# USB_Hub.net
KiCad netlist of a schematic drawn in Altium Designer
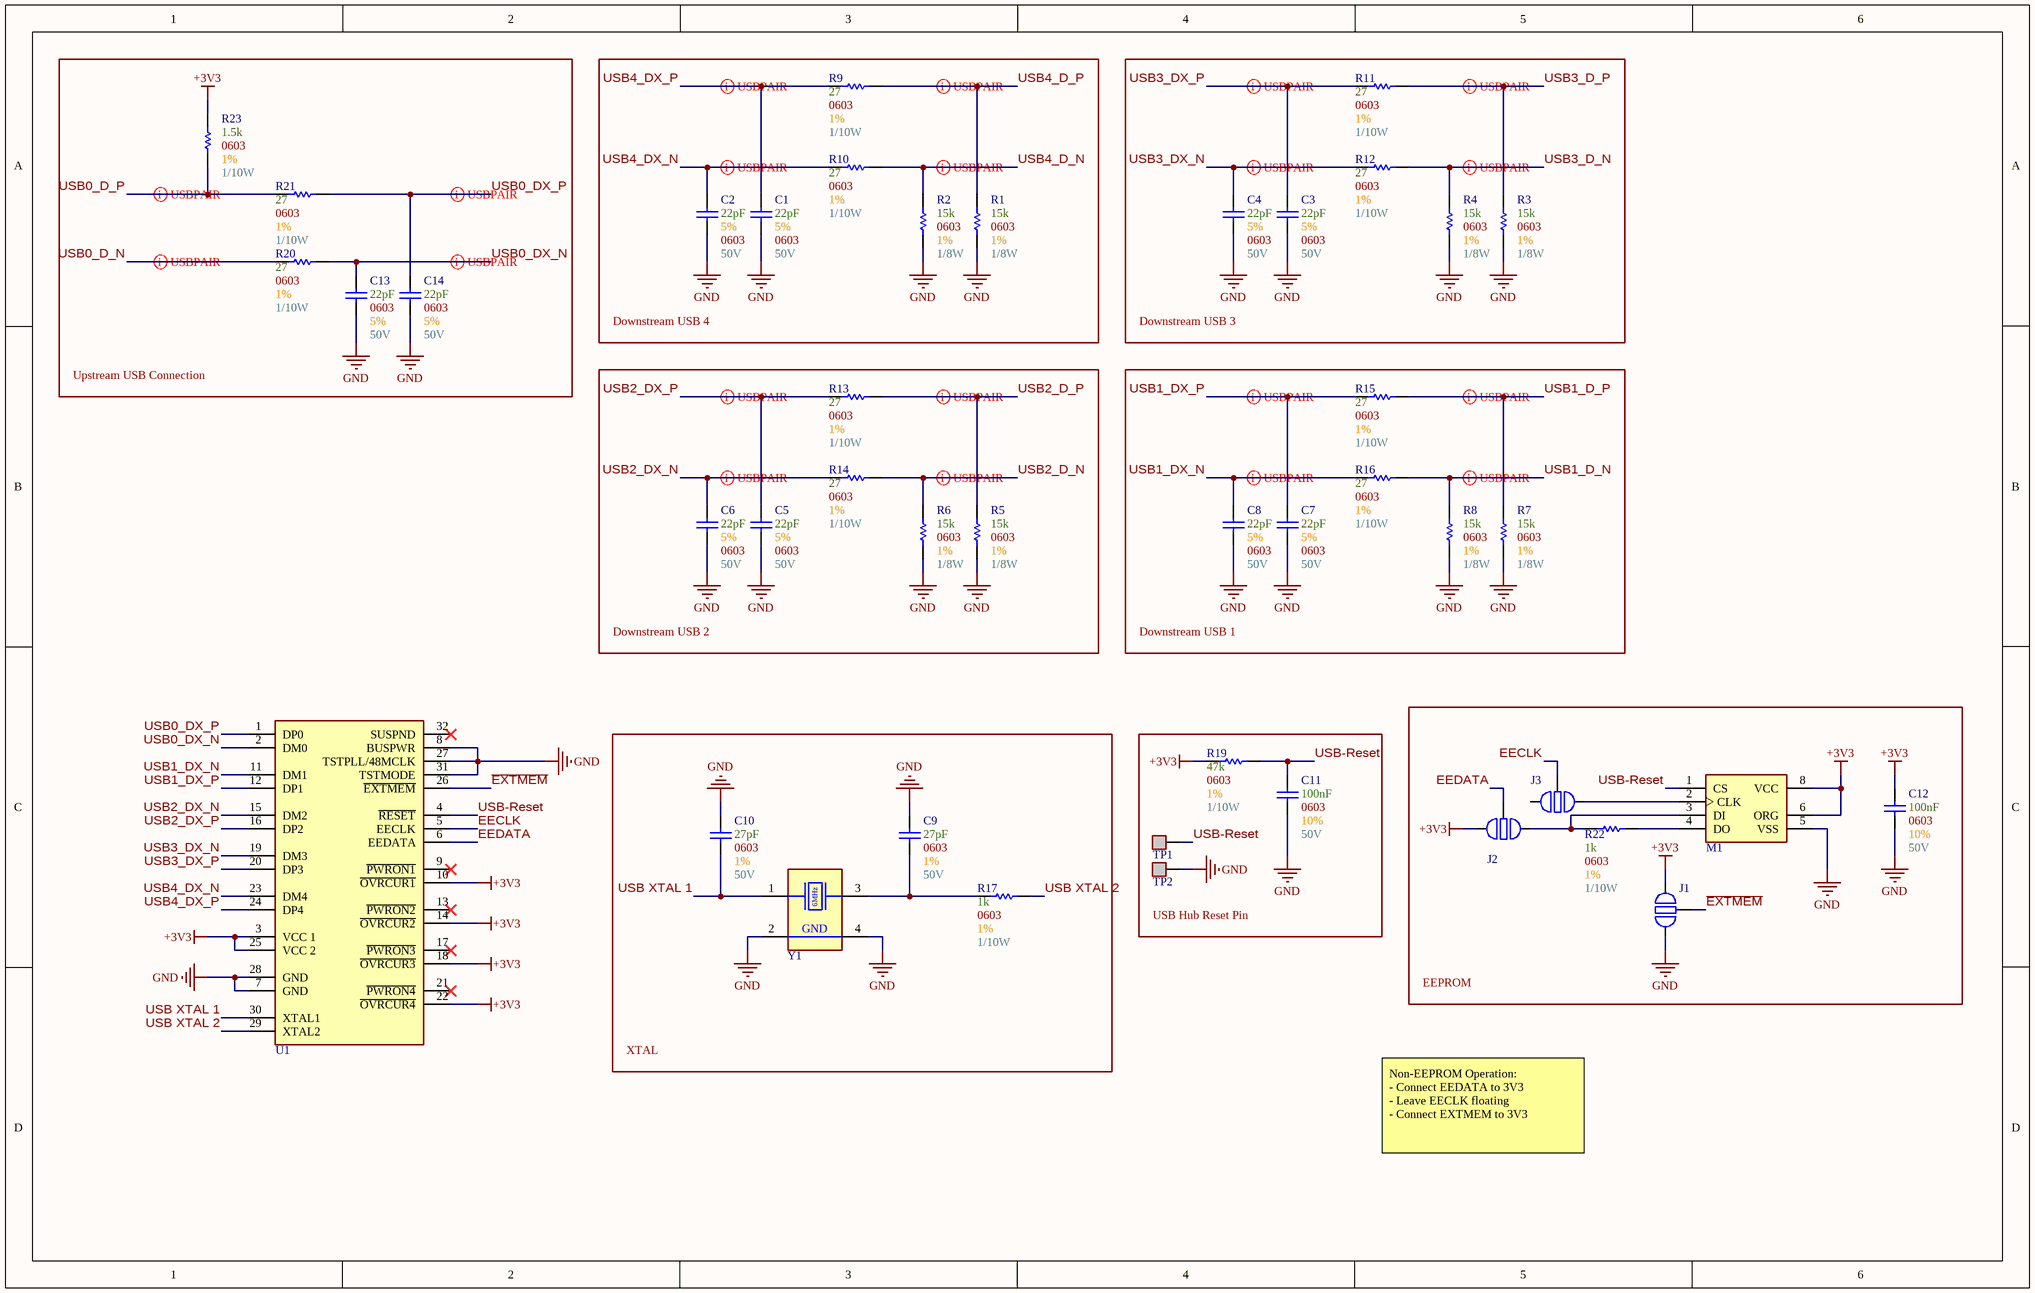
[diagram p0: USB Hub.SchDoc]

(export (version "E")
  (design (tool "Eeschema 10.0.6"))
  (components
    (comp (ref "C1")
      (value "[Cap] 0603 22pF 5% 50V")
      (footprint "[Cap] SMD 0603")
      (description "CC0603JRNPO9BN240")
      (fields
        (field (name "MAX VOLTAGE") "50V")
        (field (name "SIZE PACKAGE") "0603")
        (field (name "TOLERANCE") "5%")
        (field (name "CAPACITANCE") "22pF")
      )
      (libsource (lib "Capacitors") (part "[Cap] 0603 22pF 5% 50V"))
    )
    (comp (ref "C2")
      (value "[Cap] 0603 22pF 5% 50V")
      (footprint "[Cap] SMD 0603")
      (description "CC0603JRNPO9BN240")
      (fields
        (field (name "MAX VOLTAGE") "50V")
        (field (name "SIZE PACKAGE") "0603")
        (field (name "TOLERANCE") "5%")
        (field (name "CAPACITANCE") "22pF")
      )
      (libsource (lib "Capacitors") (part "[Cap] 0603 22pF 5% 50V"))
    )
    (comp (ref "C3")
      (value "[Cap] 0603 22pF 5% 50V")
      (footprint "[Cap] SMD 0603")
      (description "CC0603JRNPO9BN240")
      (fields
        (field (name "MAX VOLTAGE") "50V")
        (field (name "SIZE PACKAGE") "0603")
        (field (name "TOLERANCE") "5%")
        (field (name "CAPACITANCE") "22pF")
      )
      (libsource (lib "Capacitors") (part "[Cap] 0603 22pF 5% 50V"))
    )
    (comp (ref "C4")
      (value "[Cap] 0603 22pF 5% 50V")
      (footprint "[Cap] SMD 0603")
      (description "CC0603JRNPO9BN240")
      (fields
        (field (name "MAX VOLTAGE") "50V")
        (field (name "SIZE PACKAGE") "0603")
        (field (name "TOLERANCE") "5%")
        (field (name "CAPACITANCE") "22pF")
      )
      (libsource (lib "Capacitors") (part "[Cap] 0603 22pF 5% 50V"))
    )
    (comp (ref "C5")
      (value "[Cap] 0603 22pF 5% 50V")
      (footprint "[Cap] SMD 0603")
      (description "CC0603JRNPO9BN240")
      (fields
        (field (name "MAX VOLTAGE") "50V")
        (field (name "SIZE PACKAGE") "0603")
        (field (name "TOLERANCE") "5%")
        (field (name "CAPACITANCE") "22pF")
      )
      (libsource (lib "Capacitors") (part "[Cap] 0603 22pF 5% 50V"))
    )
    (comp (ref "C6")
      (value "[Cap] 0603 22pF 5% 50V")
      (footprint "[Cap] SMD 0603")
      (description "CC0603JRNPO9BN240")
      (fields
        (field (name "MAX VOLTAGE") "50V")
        (field (name "SIZE PACKAGE") "0603")
        (field (name "TOLERANCE") "5%")
        (field (name "CAPACITANCE") "22pF")
      )
      (libsource (lib "Capacitors") (part "[Cap] 0603 22pF 5% 50V"))
    )
    (comp (ref "C7")
      (value "[Cap] 0603 22pF 5% 50V")
      (footprint "[Cap] SMD 0603")
      (description "CC0603JRNPO9BN240")
      (fields
        (field (name "MAX VOLTAGE") "50V")
        (field (name "SIZE PACKAGE") "0603")
        (field (name "TOLERANCE") "5%")
        (field (name "CAPACITANCE") "22pF")
      )
      (libsource (lib "Capacitors") (part "[Cap] 0603 22pF 5% 50V"))
    )
    (comp (ref "C8")
      (value "[Cap] 0603 22pF 5% 50V")
      (footprint "[Cap] SMD 0603")
      (description "CC0603JRNPO9BN240")
      (fields
        (field (name "MAX VOLTAGE") "50V")
        (field (name "SIZE PACKAGE") "0603")
        (field (name "TOLERANCE") "5%")
        (field (name "CAPACITANCE") "22pF")
      )
      (libsource (lib "Capacitors") (part "[Cap] 0603 22pF 5% 50V"))
    )
    (comp (ref "C9")
      (value "[Cap] 0603 27pF 1% 50V")
      (footprint "[Cap] SMD 0603")
      (description "0603N270F500CT")
      (fields
        (field (name "MAX VOLTAGE") "50V")
        (field (name "SIZE PACKAGE") "0603")
        (field (name "TOLERANCE") "1%")
        (field (name "CAPACITANCE") "27pF")
      )
      (libsource (lib "Capacitors") (part "[Cap] 0603 27pF 1% 50V"))
    )
    (comp (ref "C10")
      (value "[Cap] 0603 27pF 1% 50V")
      (footprint "[Cap] SMD 0603")
      (description "0603N270F500CT")
      (fields
        (field (name "MAX VOLTAGE") "50V")
        (field (name "SIZE PACKAGE") "0603")
        (field (name "TOLERANCE") "1%")
        (field (name "CAPACITANCE") "27pF")
      )
      (libsource (lib "Capacitors") (part "[Cap] 0603 27pF 1% 50V"))
    )
    (comp (ref "C11")
      (value "[Cap] 0603 0.1uF 10% 50V")
      (footprint "[Cap] SMD 0603")
      (description "CL10B104KB8NNNC")
      (fields
        (field (name "MAX VOLTAGE") "50V")
        (field (name "SIZE PACKAGE") "0603")
        (field (name "TOLERANCE") "10%")
        (field (name "CAPACITANCE") "100nF")
      )
      (libsource (lib "Capacitors") (part "[Cap] 0603 0.1uF 10% 50V"))
    )
    (comp (ref "C12")
      (value "[Cap] 0603 0.1uF 10% 50V")
      (footprint "[Cap] SMD 0603")
      (description "CL10B104KB8NNNC")
      (fields
        (field (name "MAX VOLTAGE") "50V")
        (field (name "SIZE PACKAGE") "0603")
        (field (name "TOLERANCE") "10%")
        (field (name "CAPACITANCE") "100nF")
      )
      (libsource (lib "Capacitors") (part "[Cap] 0603 0.1uF 10% 50V"))
    )
    (comp (ref "C13")
      (value "[Cap] 0603 22pF 5% 50V")
      (footprint "[Cap] SMD 0603")
      (description "CC0603JRNPO9BN240")
      (fields
        (field (name "MAX VOLTAGE") "50V")
        (field (name "SIZE PACKAGE") "0603")
        (field (name "TOLERANCE") "5%")
        (field (name "CAPACITANCE") "22pF")
      )
      (libsource (lib "Capacitors") (part "[Cap] 0603 22pF 5% 50V"))
    )
    (comp (ref "C14")
      (value "[Cap] 0603 22pF 5% 50V")
      (footprint "[Cap] SMD 0603")
      (description "CC0603JRNPO9BN240")
      (fields
        (field (name "MAX VOLTAGE") "50V")
        (field (name "SIZE PACKAGE") "0603")
        (field (name "TOLERANCE") "5%")
        (field (name "CAPACITANCE") "22pF")
      )
      (libsource (lib "Capacitors") (part "[Cap] 0603 22pF 5% 50V"))
    )
    (comp (ref "J1")
      (value "[Jumper] Thru-Hole 3pin")
      (footprint "[Jumper] Thru-Hole 3pin")
      (libsource (lib "Misc Components") (part "[Jumper] Thru-Hole 3pin"))
    )
    (comp (ref "J2")
      (value "[Jumper] Thru-Hole 3pin")
      (footprint "[Jumper] Thru-Hole 3pin")
      (libsource (lib "Misc Components") (part "[Jumper] Thru-Hole 3pin"))
    )
    (comp (ref "J3")
      (value "[Jumper] Thru-Hole 3pin")
      (footprint "[Jumper] Thru-Hole 3pin")
      (libsource (lib "Misc Components") (part "[Jumper] Thru-Hole 3pin"))
    )
    (comp (ref "M1")
      (value "[Flash] 32x16b")
      (footprint "[Flash] 32x16b")
      (description "M93C46-WMN6TP")
      (libsource (lib "Memory") (part "[Flash] 32x16b"))
    )
    (comp (ref "R1")
      (value "[15k] SMD 0603 1% 1/8W")
      (footprint "[Res] SMD 0603")
      (description "CRCW060315K0FKEA")
      (fields
        (field (name "WATTAGE") "1/8W")
        (field (name "TOLERANCE") "1%")
        (field (name "RESISTANCE") "15k")
        (field (name "SIZE PACKAGE") "0603")
      )
      (libsource (lib "Resistors") (part "[15k] SMD 0603 1% 1/8W"))
    )
    (comp (ref "R2")
      (value "[15k] SMD 0603 1% 1/8W")
      (footprint "[Res] SMD 0603")
      (description "CRCW060315K0FKEA")
      (fields
        (field (name "WATTAGE") "1/8W")
        (field (name "TOLERANCE") "1%")
        (field (name "RESISTANCE") "15k")
        (field (name "SIZE PACKAGE") "0603")
      )
      (libsource (lib "Resistors") (part "[15k] SMD 0603 1% 1/8W"))
    )
    (comp (ref "R3")
      (value "[15k] SMD 0603 1% 1/8W")
      (footprint "[Res] SMD 0603")
      (description "CRCW060315K0FKEA")
      (fields
        (field (name "WATTAGE") "1/8W")
        (field (name "TOLERANCE") "1%")
        (field (name "RESISTANCE") "15k")
        (field (name "SIZE PACKAGE") "0603")
      )
      (libsource (lib "Resistors") (part "[15k] SMD 0603 1% 1/8W"))
    )
    (comp (ref "R4")
      (value "[15k] SMD 0603 1% 1/8W")
      (footprint "[Res] SMD 0603")
      (description "CRCW060315K0FKEA")
      (fields
        (field (name "WATTAGE") "1/8W")
        (field (name "TOLERANCE") "1%")
        (field (name "RESISTANCE") "15k")
        (field (name "SIZE PACKAGE") "0603")
      )
      (libsource (lib "Resistors") (part "[15k] SMD 0603 1% 1/8W"))
    )
    (comp (ref "R5")
      (value "[15k] SMD 0603 1% 1/8W")
      (footprint "[Res] SMD 0603")
      (description "CRCW060315K0FKEA")
      (fields
        (field (name "WATTAGE") "1/8W")
        (field (name "TOLERANCE") "1%")
        (field (name "RESISTANCE") "15k")
        (field (name "SIZE PACKAGE") "0603")
      )
      (libsource (lib "Resistors") (part "[15k] SMD 0603 1% 1/8W"))
    )
    (comp (ref "R6")
      (value "[15k] SMD 0603 1% 1/8W")
      (footprint "[Res] SMD 0603")
      (description "CRCW060315K0FKEA")
      (fields
        (field (name "WATTAGE") "1/8W")
        (field (name "TOLERANCE") "1%")
        (field (name "RESISTANCE") "15k")
        (field (name "SIZE PACKAGE") "0603")
      )
      (libsource (lib "Resistors") (part "[15k] SMD 0603 1% 1/8W"))
    )
    (comp (ref "R7")
      (value "[15k] SMD 0603 1% 1/8W")
      (footprint "[Res] SMD 0603")
      (description "CRCW060315K0FKEA")
      (fields
        (field (name "WATTAGE") "1/8W")
        (field (name "TOLERANCE") "1%")
        (field (name "RESISTANCE") "15k")
        (field (name "SIZE PACKAGE") "0603")
      )
      (libsource (lib "Resistors") (part "[15k] SMD 0603 1% 1/8W"))
    )
    (comp (ref "R8")
      (value "[15k] SMD 0603 1% 1/8W")
      (footprint "[Res] SMD 0603")
      (description "CRCW060315K0FKEA")
      (fields
        (field (name "WATTAGE") "1/8W")
        (field (name "TOLERANCE") "1%")
        (field (name "RESISTANCE") "15k")
        (field (name "SIZE PACKAGE") "0603")
      )
      (libsource (lib "Resistors") (part "[15k] SMD 0603 1% 1/8W"))
    )
    (comp (ref "R9")
      (value "[27] SMD 0603 1% 1/10W")
      (footprint "[Res] SMD 0603")
      (description "MCT06030C2709FP500")
      (fields
        (field (name "WATTAGE") "1/10W")
        (field (name "TOLERANCE") "1%")
        (field (name "RESISTANCE") "27")
        (field (name "SIZE PACKAGE") "0603")
      )
      (libsource (lib "Resistors") (part "[27] SMD 0603 1% 1/10W"))
    )
    (comp (ref "R10")
      (value "[27] SMD 0603 1% 1/10W")
      (footprint "[Res] SMD 0603")
      (description "MCT06030C2709FP500")
      (fields
        (field (name "WATTAGE") "1/10W")
        (field (name "TOLERANCE") "1%")
        (field (name "RESISTANCE") "27")
        (field (name "SIZE PACKAGE") "0603")
      )
      (libsource (lib "Resistors") (part "[27] SMD 0603 1% 1/10W"))
    )
    (comp (ref "R11")
      (value "[27] SMD 0603 1% 1/10W")
      (footprint "[Res] SMD 0603")
      (description "MCT06030C2709FP500")
      (fields
        (field (name "WATTAGE") "1/10W")
        (field (name "TOLERANCE") "1%")
        (field (name "RESISTANCE") "27")
        (field (name "SIZE PACKAGE") "0603")
      )
      (libsource (lib "Resistors") (part "[27] SMD 0603 1% 1/10W"))
    )
    (comp (ref "R12")
      (value "[27] SMD 0603 1% 1/10W")
      (footprint "[Res] SMD 0603")
      (description "MCT06030C2709FP500")
      (fields
        (field (name "WATTAGE") "1/10W")
        (field (name "TOLERANCE") "1%")
        (field (name "RESISTANCE") "27")
        (field (name "SIZE PACKAGE") "0603")
      )
      (libsource (lib "Resistors") (part "[27] SMD 0603 1% 1/10W"))
    )
    (comp (ref "R13")
      (value "[27] SMD 0603 1% 1/10W")
      (footprint "[Res] SMD 0603")
      (description "MCT06030C2709FP500")
      (fields
        (field (name "WATTAGE") "1/10W")
        (field (name "TOLERANCE") "1%")
        (field (name "RESISTANCE") "27")
        (field (name "SIZE PACKAGE") "0603")
      )
      (libsource (lib "Resistors") (part "[27] SMD 0603 1% 1/10W"))
    )
    (comp (ref "R14")
      (value "[27] SMD 0603 1% 1/10W")
      (footprint "[Res] SMD 0603")
      (description "MCT06030C2709FP500")
      (fields
        (field (name "WATTAGE") "1/10W")
        (field (name "TOLERANCE") "1%")
        (field (name "RESISTANCE") "27")
        (field (name "SIZE PACKAGE") "0603")
      )
      (libsource (lib "Resistors") (part "[27] SMD 0603 1% 1/10W"))
    )
    (comp (ref "R15")
      (value "[27] SMD 0603 1% 1/10W")
      (footprint "[Res] SMD 0603")
      (description "MCT06030C2709FP500")
      (fields
        (field (name "WATTAGE") "1/10W")
        (field (name "TOLERANCE") "1%")
        (field (name "RESISTANCE") "27")
        (field (name "SIZE PACKAGE") "0603")
      )
      (libsource (lib "Resistors") (part "[27] SMD 0603 1% 1/10W"))
    )
    (comp (ref "R16")
      (value "[27] SMD 0603 1% 1/10W")
      (footprint "[Res] SMD 0603")
      (description "MCT06030C2709FP500")
      (fields
        (field (name "WATTAGE") "1/10W")
        (field (name "TOLERANCE") "1%")
        (field (name "RESISTANCE") "27")
        (field (name "SIZE PACKAGE") "0603")
      )
      (libsource (lib "Resistors") (part "[27] SMD 0603 1% 1/10W"))
    )
    (comp (ref "R17")
      (value "[1k] SMD 0603 1% 1/10W")
      (footprint "[Res] SMD 0603")
      (description "RMCF0603FT1K00")
      (fields
        (field (name "WATTAGE") "1/10W")
        (field (name "TOLERANCE") "1%")
        (field (name "RESISTANCE") "1k")
        (field (name "SIZE PACKAGE") "0603")
      )
      (libsource (lib "Resistors") (part "[1k] SMD 0603 1% 1/10W"))
    )
    (comp (ref "R19")
      (value "[47k] SMD 0603 1% 1/10W")
      (footprint "[Res] SMD 0603")
      (description "RC0603FR-0747KL")
      (fields
        (field (name "WATTAGE") "1/10W")
        (field (name "TOLERANCE") "1%")
        (field (name "RESISTANCE") "47k")
        (field (name "SIZE PACKAGE") "0603")
      )
      (libsource (lib "Resistors") (part "[47k] SMD 0603 1% 1/10W"))
    )
    (comp (ref "R20")
      (value "[27] SMD 0603 1% 1/10W")
      (footprint "[Res] SMD 0603")
      (description "MCT06030C2709FP500")
      (fields
        (field (name "WATTAGE") "1/10W")
        (field (name "TOLERANCE") "1%")
        (field (name "RESISTANCE") "27")
        (field (name "SIZE PACKAGE") "0603")
      )
      (libsource (lib "Resistors") (part "[27] SMD 0603 1% 1/10W"))
    )
    (comp (ref "R21")
      (value "[27] SMD 0603 1% 1/10W")
      (footprint "[Res] SMD 0603")
      (description "MCT06030C2709FP500")
      (fields
        (field (name "WATTAGE") "1/10W")
        (field (name "TOLERANCE") "1%")
        (field (name "RESISTANCE") "27")
        (field (name "SIZE PACKAGE") "0603")
      )
      (libsource (lib "Resistors") (part "[27] SMD 0603 1% 1/10W"))
    )
    (comp (ref "R22")
      (value "[1k] SMD 0603 1% 1/10W")
      (footprint "[Res] SMD 0603")
      (description "RMCF0603FT1K00")
      (fields
        (field (name "WATTAGE") "1/10W")
        (field (name "TOLERANCE") "1%")
        (field (name "RESISTANCE") "1k")
        (field (name "SIZE PACKAGE") "0603")
      )
      (libsource (lib "Resistors") (part "[1k] SMD 0603 1% 1/10W"))
    )
    (comp (ref "R23")
      (value "[1.5k] SMD 0603 1% 1/10W")
      (footprint "[Res] SMD 0603")
      (description "CR0603-FX-1501ELF")
      (fields
        (field (name "WATTAGE") "1/10W")
        (field (name "TOLERANCE") "1%")
        (field (name "RESISTANCE") "1.5k")
        (field (name "SIZE PACKAGE") "0603")
      )
      (libsource (lib "Resistors") (part "[1.5k] SMD 0603 1% 1/10W"))
    )
    (comp (ref "TP1")
      (value "[THM] Thru-Hole")
      (footprint "[THM] White")
      (description "5012")
      (libsource (lib "Test Points") (part "[THM] Thru-Hole"))
    )
    (comp (ref "TP2")
      (value "[THM] Thru-Hole")
      (footprint "[THM] White")
      (description "5012")
      (libsource (lib "Test Points") (part "[THM] Thru-Hole"))
    )
    (comp (ref "U1")
      (value "4port")
      (footprint "[USB Hub] USB2.0 4port")
      (description "TUSB2046BVFR")
      (libsource (lib "ICs") (part "[USB Hub] USB 2.0 4port"))
    )
    (comp (ref "Y1")
      (value "[Crystal] SMD 6MHz")
      (footprint "[Crystal] SMD 6MHz")
      (description "ECS-060-18-20BM-JEN-TR")
      (libsource (lib "Crystals and Oscillators") (part "[Crystal] SMD 6MHz"))
    )
  )
  (nets
    (net (code "1") (name "+3V3") (class "Default")
      (node (ref "C12") (pin "2") (pinfunction "2_2") (pintype "passive"))
      (node (ref "J1") (pin "3") (pintype "passive"))
      (node (ref "J2") (pin "3") (pintype "passive"))
      (node (ref "M1") (pin "6") (pinfunction "ORG_6") (pintype "passive"))
      (node (ref "M1") (pin "8") (pinfunction "VCC_8") (pintype "passive"))
      (node (ref "R19") (pin "1") (pinfunction "1_1") (pintype "passive"))
      (node (ref "R23") (pin "2") (pinfunction "2_2") (pintype "passive"))
      (node (ref "U1") (pin "10") (pinfunction "~{OVRCUR1}_10") (pintype "passive"))
      (node (ref "U1") (pin "14") (pinfunction "~{OVRCUR2}_14") (pintype "passive"))
      (node (ref "U1") (pin "18") (pinfunction "~{OVRCUR3}_18") (pintype "passive"))
      (node (ref "U1") (pin "22") (pinfunction "~{OVRCUR4}_22") (pintype "passive"))
      (node (ref "U1") (pin "25") (pinfunction "VCC_2_25") (pintype "passive"))
      (node (ref "U1") (pin "3") (pinfunction "VCC_1_3") (pintype "passive"))
    )
    (net (code "2") (name "/EECLK") (class "Default")
      (node (ref "J3") (pin "2") (pinfunction "Common_2") (pintype "power_in"))
      (node (ref "U1") (pin "5") (pinfunction "EECLK_5") (pintype "passive"))
    )
    (net (code "3") (name "/EEDATA") (class "Default")
      (node (ref "J2") (pin "2") (pinfunction "Common_2") (pintype "power_in"))
      (node (ref "U1") (pin "6") (pinfunction "EEDATA_6") (pintype "passive"))
    )
    (net (code "4") (name "/EXTMEM") (class "Default")
      (node (ref "J1") (pin "2") (pinfunction "Common_2") (pintype "power_in"))
      (node (ref "U1") (pin "26") (pinfunction "~{EXTMEM}_26") (pintype "passive"))
    )
    (net (code "5") (name "/USB XTAL 1") (class "Default")
      (node (ref "C10") (pin "2") (pinfunction "2_2") (pintype "passive"))
      (node (ref "U1") (pin "30") (pinfunction "XTAL1_30") (pintype "passive"))
      (node (ref "Y1") (pin "1") (pinfunction "XTAL1_1") (pintype "power_in"))
    )
    (net (code "6") (name "/USB XTAL 2") (class "Default")
      (node (ref "R17") (pin "2") (pinfunction "2_2") (pintype "passive"))
      (node (ref "U1") (pin "29") (pinfunction "XTAL2_29") (pintype "passive"))
    )
    (net (code "7") (name "/USB-Reset") (class "Default")
      (node (ref "C11") (pin "2") (pinfunction "2_2") (pintype "passive"))
      (node (ref "M1") (pin "1") (pinfunction "CS_1") (pintype "passive"))
      (node (ref "R19") (pin "2") (pinfunction "2_2") (pintype "passive"))
      (node (ref "TP1") (pin "1") (pinfunction "1_1") (pintype "passive"))
      (node (ref "U1") (pin "4") (pinfunction "~{RESET}_4") (pintype "passive"))
    )
    (net (code "8") (name "/USB0_DX_N") (class "Default")
      (node (ref "C13") (pin "2") (pinfunction "2_2") (pintype "passive"))
      (node (ref "R20") (pin "2") (pinfunction "2_2") (pintype "passive"))
      (node (ref "U1") (pin "2") (pinfunction "DM0_2") (pintype "passive"))
    )
    (net (code "9") (name "/USB0_DX_P") (class "Default")
      (node (ref "C14") (pin "2") (pinfunction "2_2") (pintype "passive"))
      (node (ref "R21") (pin "2") (pinfunction "2_2") (pintype "passive"))
      (node (ref "U1") (pin "1") (pinfunction "DP0_1") (pintype "passive"))
    )
    (net (code "10") (name "/USB0_D_N") (class "Default")
      (node (ref "R20") (pin "1") (pinfunction "1_1") (pintype "passive"))
    )
    (net (code "11") (name "/USB0_D_P") (class "Default")
      (node (ref "R21") (pin "1") (pinfunction "1_1") (pintype "passive"))
      (node (ref "R23") (pin "1") (pinfunction "1_1") (pintype "passive"))
    )
    (net (code "12") (name "/USB1_DX_N") (class "Default")
      (node (ref "C8") (pin "2") (pinfunction "2_2") (pintype "passive"))
      (node (ref "R16") (pin "1") (pinfunction "1_1") (pintype "passive"))
      (node (ref "U1") (pin "11") (pinfunction "DM1_11") (pintype "passive"))
    )
    (net (code "13") (name "/USB1_DX_P") (class "Default")
      (node (ref "C7") (pin "2") (pinfunction "2_2") (pintype "passive"))
      (node (ref "R15") (pin "1") (pinfunction "1_1") (pintype "passive"))
      (node (ref "U1") (pin "12") (pinfunction "DP1_12") (pintype "passive"))
    )
    (net (code "14") (name "/USB1_D_N") (class "Default")
      (node (ref "R16") (pin "2") (pinfunction "2_2") (pintype "passive"))
      (node (ref "R8") (pin "2") (pinfunction "2_2") (pintype "passive"))
    )
    (net (code "15") (name "/USB1_D_P") (class "Default")
      (node (ref "R15") (pin "2") (pinfunction "2_2") (pintype "passive"))
      (node (ref "R7") (pin "2") (pinfunction "2_2") (pintype "passive"))
    )
    (net (code "16") (name "/USB2_DX_N") (class "Default")
      (node (ref "C6") (pin "2") (pinfunction "2_2") (pintype "passive"))
      (node (ref "R14") (pin "1") (pinfunction "1_1") (pintype "passive"))
      (node (ref "U1") (pin "15") (pinfunction "DM2_15") (pintype "passive"))
    )
    (net (code "17") (name "/USB2_DX_P") (class "Default")
      (node (ref "C5") (pin "2") (pinfunction "2_2") (pintype "passive"))
      (node (ref "R13") (pin "1") (pinfunction "1_1") (pintype "passive"))
      (node (ref "U1") (pin "16") (pinfunction "DP2_16") (pintype "passive"))
    )
    (net (code "18") (name "/USB2_D_N") (class "Default")
      (node (ref "R14") (pin "2") (pinfunction "2_2") (pintype "passive"))
      (node (ref "R6") (pin "2") (pinfunction "2_2") (pintype "passive"))
    )
    (net (code "19") (name "/USB2_D_P") (class "Default")
      (node (ref "R13") (pin "2") (pinfunction "2_2") (pintype "passive"))
      (node (ref "R5") (pin "2") (pinfunction "2_2") (pintype "passive"))
    )
    (net (code "20") (name "/USB3_DX_N") (class "Default")
      (node (ref "C4") (pin "2") (pinfunction "2_2") (pintype "passive"))
      (node (ref "R12") (pin "1") (pinfunction "1_1") (pintype "passive"))
      (node (ref "U1") (pin "19") (pinfunction "DM3_19") (pintype "passive"))
    )
    (net (code "21") (name "/USB3_DX_P") (class "Default")
      (node (ref "C3") (pin "2") (pinfunction "2_2") (pintype "passive"))
      (node (ref "R11") (pin "1") (pinfunction "1_1") (pintype "passive"))
      (node (ref "U1") (pin "20") (pinfunction "DP3_20") (pintype "passive"))
    )
    (net (code "22") (name "/USB3_D_N") (class "Default")
      (node (ref "R12") (pin "2") (pinfunction "2_2") (pintype "passive"))
      (node (ref "R4") (pin "2") (pinfunction "2_2") (pintype "passive"))
    )
    (net (code "23") (name "/USB3_D_P") (class "Default")
      (node (ref "R11") (pin "2") (pinfunction "2_2") (pintype "passive"))
      (node (ref "R3") (pin "2") (pinfunction "2_2") (pintype "passive"))
    )
    (net (code "24") (name "/USB4_DX_N") (class "Default")
      (node (ref "C2") (pin "2") (pinfunction "2_2") (pintype "passive"))
      (node (ref "R10") (pin "1") (pinfunction "1_1") (pintype "passive"))
      (node (ref "U1") (pin "23") (pinfunction "DM4_23") (pintype "passive"))
    )
    (net (code "25") (name "/USB4_DX_P") (class "Default")
      (node (ref "C1") (pin "2") (pinfunction "2_2") (pintype "passive"))
      (node (ref "R9") (pin "1") (pinfunction "1_1") (pintype "passive"))
      (node (ref "U1") (pin "24") (pinfunction "DP4_24") (pintype "passive"))
    )
    (net (code "26") (name "/USB4_D_N") (class "Default")
      (node (ref "R10") (pin "2") (pinfunction "2_2") (pintype "passive"))
      (node (ref "R2") (pin "2") (pinfunction "2_2") (pintype "passive"))
    )
    (net (code "27") (name "/USB4_D_P") (class "Default")
      (node (ref "R1") (pin "2") (pinfunction "2_2") (pintype "passive"))
      (node (ref "R9") (pin "2") (pinfunction "2_2") (pintype "passive"))
    )
    (net (code "28") (name "GND") (class "Default")
      (node (ref "C1") (pin "1") (pinfunction "1_1") (pintype "passive"))
      (node (ref "C10") (pin "1") (pinfunction "1_1") (pintype "passive"))
      (node (ref "C11") (pin "1") (pinfunction "1_1") (pintype "passive"))
      (node (ref "C12") (pin "1") (pinfunction "1_1") (pintype "passive"))
      (node (ref "C13") (pin "1") (pinfunction "1_1") (pintype "passive"))
      (node (ref "C14") (pin "1") (pinfunction "1_1") (pintype "passive"))
      (node (ref "C2") (pin "1") (pinfunction "1_1") (pintype "passive"))
      (node (ref "C3") (pin "1") (pinfunction "1_1") (pintype "passive"))
      (node (ref "C4") (pin "1") (pinfunction "1_1") (pintype "passive"))
      (node (ref "C5") (pin "1") (pinfunction "1_1") (pintype "passive"))
      (node (ref "C6") (pin "1") (pinfunction "1_1") (pintype "passive"))
      (node (ref "C7") (pin "1") (pinfunction "1_1") (pintype "passive"))
      (node (ref "C8") (pin "1") (pinfunction "1_1") (pintype "passive"))
      (node (ref "C9") (pin "1") (pinfunction "1_1") (pintype "passive"))
      (node (ref "J1") (pin "1") (pintype "passive"))
      (node (ref "M1") (pin "5") (pinfunction "VSS_5") (pintype "passive"))
      (node (ref "R1") (pin "1") (pinfunction "1_1") (pintype "passive"))
      (node (ref "R2") (pin "1") (pinfunction "1_1") (pintype "passive"))
      (node (ref "R3") (pin "1") (pinfunction "1_1") (pintype "passive"))
      (node (ref "R4") (pin "1") (pinfunction "1_1") (pintype "passive"))
      (node (ref "R5") (pin "1") (pinfunction "1_1") (pintype "passive"))
      (node (ref "R6") (pin "1") (pinfunction "1_1") (pintype "passive"))
      (node (ref "R7") (pin "1") (pinfunction "1_1") (pintype "passive"))
      (node (ref "R8") (pin "1") (pinfunction "1_1") (pintype "passive"))
      (node (ref "TP2") (pin "1") (pinfunction "1_1") (pintype "passive"))
      (node (ref "U1") (pin "27") (pinfunction "TSTPLL/48MCLK_27") (pintype "passive"))
      (node (ref "U1") (pin "28") (pinfunction "GND_28") (pintype "passive"))
      (node (ref "U1") (pin "31") (pinfunction "TSTMODE_31") (pintype "passive"))
      (node (ref "U1") (pin "7") (pinfunction "GND_7") (pintype "passive"))
      (node (ref "U1") (pin "8") (pinfunction "BUSPWR_8") (pintype "passive"))
      (node (ref "Y1") (pin "2") (pinfunction "GND_2") (pintype "power_in"))
      (node (ref "Y1") (pin "4") (pinfunction "GND_4") (pintype "power_in"))
    )
    (net (code "29") (name "Net-(M1-CLK)") (class "Default")
      (node (ref "J3") (pin "1") (pintype "passive"))
      (node (ref "M1") (pin "2") (pinfunction "CLK_2") (pintype "passive"))
    )
    (net (code "30") (name "Net-(M1-DI)") (class "Default")
      (node (ref "J2") (pin "1") (pintype "passive"))
      (node (ref "M1") (pin "3") (pinfunction "DI_3") (pintype "passive"))
      (node (ref "R22") (pin "2") (pinfunction "2_2") (pintype "passive"))
    )
    (net (code "31") (name "Net-(M1-DO)") (class "Default")
      (node (ref "M1") (pin "4") (pinfunction "DO_4") (pintype "passive"))
      (node (ref "R22") (pin "1") (pinfunction "1_1") (pintype "passive"))
    )
    (net (code "32") (name "Net-(Y1-XTAL2)") (class "Default")
      (node (ref "C9") (pin "2") (pinfunction "2_2") (pintype "passive"))
      (node (ref "R17") (pin "1") (pinfunction "1_1") (pintype "passive"))
      (node (ref "Y1") (pin "3") (pinfunction "XTAL2_3") (pintype "power_in"))
    )
    (net (code "33") (name "unconnected-(J3-Pad3)") (class "Default")
      (node (ref "J3") (pin "3") (pintype "passive"))
    )
    (net (code "34") (name "unconnected-(U1-SUSPND-Pad32)") (class "Default")
      (node (ref "U1") (pin "32") (pinfunction "SUSPND_32") (pintype "passive+no_connect"))
    )
    (net (code "35") (name "unconnected-(U1-~{PWRON1}-Pad9)") (class "Default")
      (node (ref "U1") (pin "9") (pinfunction "~{PWRON1}_9") (pintype "passive+no_connect"))
    )
    (net (code "36") (name "unconnected-(U1-~{PWRON2}-Pad13)") (class "Default")
      (node (ref "U1") (pin "13") (pinfunction "~{PWRON2}_13") (pintype "passive+no_connect"))
    )
    (net (code "37") (name "unconnected-(U1-~{PWRON3}-Pad17)") (class "Default")
      (node (ref "U1") (pin "17") (pinfunction "~{PWRON3}_17") (pintype "passive+no_connect"))
    )
    (net (code "38") (name "unconnected-(U1-~{PWRON4}-Pad21)") (class "Default")
      (node (ref "U1") (pin "21") (pinfunction "~{PWRON4}_21") (pintype "passive+no_connect"))
    )
  )
)
